# shrp-001.net
KiCad netlist of a schematic drawn in EAGLE
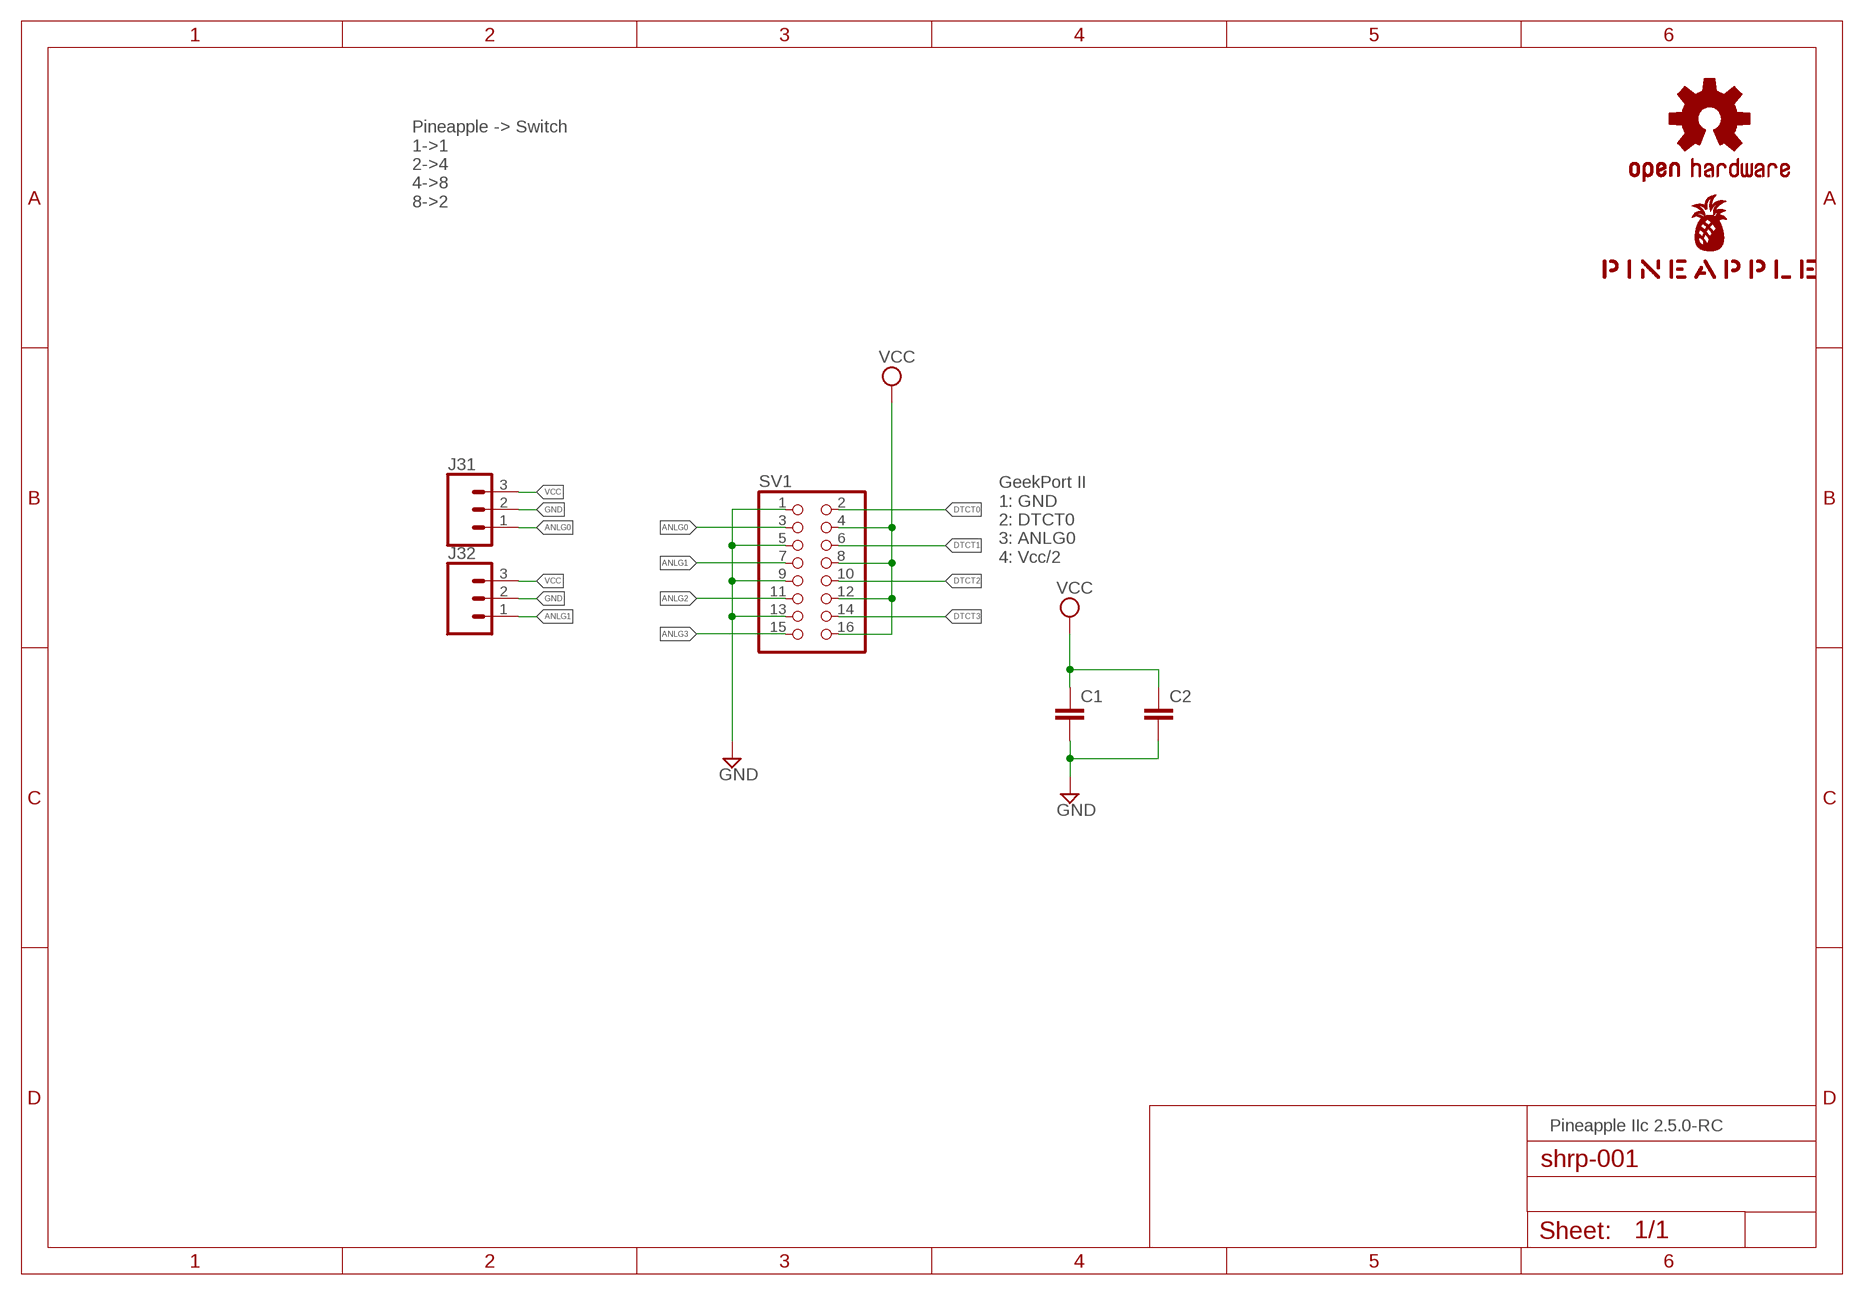
[diagram p0: schematic, sheet 1]

(export (version "E")
  (design (tool "Eeschema 10.0.6"))
  (components
    (comp (ref "C1")
      (value "C-EU025-024X044")
      (footprint "eagle-import:C025-024X044")
      (libsource (lib "eagle-import") (part "C-EU025-024X044"))
    )
    (comp (ref "C2")
      (value "C-EU025-024X044")
      (footprint "eagle-import:C025-024X044")
      (libsource (lib "eagle-import") (part "C-EU025-024X044"))
    )
    (comp (ref "J31")
      (value "CONN_03JST-PTH")
      (footprint "eagle-import:JST-3-PTH")
      (libsource (lib "eagle-import") (part "CONN_03JST-PTH"))
    )
    (comp (ref "J32")
      (value "CONN_03JST-PTH")
      (footprint "eagle-import:JST-3-PTH")
      (libsource (lib "eagle-import") (part "CONN_03JST-PTH"))
    )
    (comp (ref "LOGO1")
      (value "OSHW-LOGOS-COPPER")
      (footprint "eagle-import:OSHW-LOGO-S_COPPER")
      (libsource (lib "eagle-import") (part "OSHW-LOGOS-COPPER"))
    )
    (comp (ref "SV1")
      (value "PINHD-2X8")
      (footprint "eagle-import:2X08")
      (libsource (lib "eagle-import") (part "PINHD-2X8"))
    )
    (comp (ref "U$1")
      (value "PINEAPPLE450_SILK")
      (footprint "eagle-import:PINEAPPLE450_SILK")
      (libsource (lib "eagle-import") (part "PINEAPPLE450_SILK"))
    )
  )
  (nets
    (net (code "1") (name "ANLG0") (class "Default")
      (node (ref "J31") (pin "1") (pinfunction "1_1") (pintype "passive"))
      (node (ref "SV1") (pin "3") (pinfunction "3_3") (pintype "passive"))
    )
    (net (code "2") (name "ANLG1") (class "Default")
      (node (ref "J32") (pin "1") (pinfunction "1_1") (pintype "passive"))
      (node (ref "SV1") (pin "7") (pinfunction "7_7") (pintype "passive"))
    )
    (net (code "3") (name "ANLG2") (class "Default")
      (node (ref "SV1") (pin "11") (pinfunction "11_11") (pintype "passive"))
    )
    (net (code "4") (name "ANLG3") (class "Default")
      (node (ref "SV1") (pin "15") (pinfunction "15_15") (pintype "passive"))
    )
    (net (code "5") (name "DTCT0") (class "Default")
      (node (ref "SV1") (pin "2") (pinfunction "2_2") (pintype "passive"))
    )
    (net (code "6") (name "DTCT1") (class "Default")
      (node (ref "SV1") (pin "6") (pinfunction "6_6") (pintype "passive"))
    )
    (net (code "7") (name "DTCT2") (class "Default")
      (node (ref "SV1") (pin "10") (pinfunction "10_10") (pintype "passive"))
    )
    (net (code "8") (name "DTCT3") (class "Default")
      (node (ref "SV1") (pin "14") (pinfunction "14_14") (pintype "passive"))
    )
    (net (code "9") (name "GND") (class "Default")
      (node (ref "C1") (pin "2") (pinfunction "2_2") (pintype "passive"))
      (node (ref "C2") (pin "2") (pinfunction "2_2") (pintype "passive"))
      (node (ref "J31") (pin "2") (pinfunction "2_2") (pintype "passive"))
      (node (ref "J32") (pin "2") (pinfunction "2_2") (pintype "passive"))
      (node (ref "SV1") (pin "1") (pinfunction "1_1") (pintype "passive"))
      (node (ref "SV1") (pin "13") (pinfunction "13_13") (pintype "passive"))
      (node (ref "SV1") (pin "5") (pinfunction "5_5") (pintype "passive"))
      (node (ref "SV1") (pin "9") (pinfunction "9_9") (pintype "passive"))
    )
    (net (code "10") (name "VCC") (class "Default")
      (node (ref "C1") (pin "1") (pinfunction "1_1") (pintype "passive"))
      (node (ref "C2") (pin "1") (pinfunction "1_1") (pintype "passive"))
      (node (ref "J31") (pin "3") (pinfunction "3_3") (pintype "passive"))
      (node (ref "J32") (pin "3") (pinfunction "3_3") (pintype "passive"))
      (node (ref "SV1") (pin "12") (pinfunction "12_12") (pintype "passive"))
      (node (ref "SV1") (pin "16") (pinfunction "16_16") (pintype "passive"))
      (node (ref "SV1") (pin "4") (pinfunction "4_4") (pintype "passive"))
      (node (ref "SV1") (pin "8") (pinfunction "8_8") (pintype "passive"))
    )
  )
)
